# Line_Sensor.net
KiCad netlist of a schematic drawn in Altium Designer
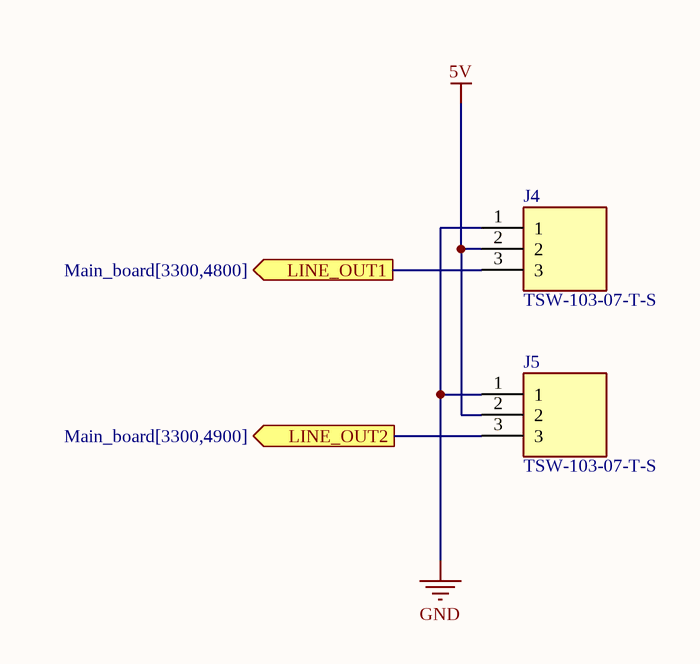
[diagram p0: Line_Sensor.SchDoc]

(export (version "E")
  (design (tool "Eeschema 10.0.6"))
  (components
    (comp (ref "J4")
      (value "TSW-103-07-T-S")
      (footprint "PCB 3 PIN PADS")
      (description "Connector")
      (fields (field (name "MOUSER PART NUMBER") "200-TSW10307TS"))
      (libsource (lib "SamacSys") (part "TSW-103-07-T-S"))
    )
    (comp (ref "J5")
      (value "TSW-103-07-T-S")
      (footprint "PCB 3 PIN PADS")
      (description "Connector")
      (fields (field (name "MOUSER PART NUMBER") "200-TSW10307TS"))
      (libsource (lib "SamacSys") (part "TSW-103-07-T-S"))
    )
  )
  (nets
    (net (code "1") (name "/LINE_OUT1") (class "Default")
      (node (ref "J4") (pin "3") (pinfunction "3_3") (pintype "passive"))
    )
    (net (code "2") (name "/LINE_OUT2") (class "Default")
      (node (ref "J5") (pin "3") (pinfunction "3_3") (pintype "passive"))
    )
    (net (code "3") (name "5V") (class "Default")
      (node (ref "J4") (pin "2") (pinfunction "2_2") (pintype "passive"))
      (node (ref "J5") (pin "2") (pinfunction "2_2") (pintype "passive"))
    )
    (net (code "4") (name "GND") (class "Default")
      (node (ref "J4") (pin "1") (pinfunction "1_1") (pintype "passive"))
      (node (ref "J5") (pin "1") (pinfunction "1_1") (pintype "passive"))
    )
  )
)
